# try.net
KiCad netlist of a schematic drawn in EAGLE
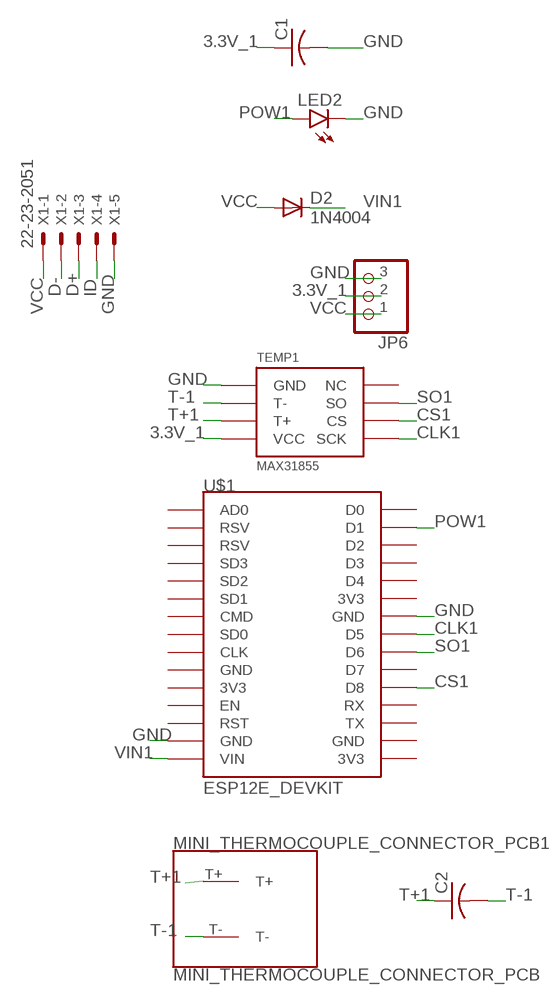
[diagram p0: schematic, sheet 1]

(export (version "E")
  (design (tool "Eeschema 10.0.6"))
  (components
    (comp (ref "C1")
      (value "C-US025-040X050")
      (footprint "eagle-import:C025-040X050")
      (libsource (lib "eagle-import") (part "C-US025-040X050"))
    )
    (comp (ref "C2")
      (value "C-US025-040X050")
      (footprint "eagle-import:C025-040X050")
      (libsource (lib "eagle-import") (part "C-US025-040X050"))
    )
    (comp (ref "D2")
      (value "1N4004")
      (footprint "eagle-import:DO41-10")
      (libsource (lib "eagle-import") (part "1N4004"))
    )
    (comp (ref "JP6")
      (value "PINHD-1X3CB")
      (footprint "eagle-import:1X03-CLEANBIG")
      (libsource (lib "eagle-import") (part "PINHD-1X3CB"))
    )
    (comp (ref "LED2")
      (value "LED5MM")
      (footprint "eagle-import:LED5MM")
      (libsource (lib "eagle-import") (part "LED5MM"))
    )
    (comp (ref "MINI_THERMOCOUPLE_CONNECTOR_PCB1")
      (value "MINI_THERMOCOUPLE_CONNECTOR_PCB")
      (footprint "eagle-import:MINI_THERMOCOUPLE_CONNECTOR_PCB")
      (libsource (lib "eagle-import") (part "MINI_THERMOCOUPLE_CONNECTOR_PCB"))
    )
    (comp (ref "TEMP1")
      (value "MAX31855")
      (footprint "eagle-import:SOIC-8")
      (libsource (lib "eagle-import") (part "MAX6675MAX31855"))
    )
    (comp (ref "U$1")
      (value "ESP12E_DEVKIT")
      (footprint "eagle-import:ESP12E_DEVKIT")
      (libsource (lib "eagle-import") (part "ESP12E_DEVKIT"))
    )
    (comp (ref "X1")
      (value "22-23-2051")
      (footprint "eagle-import:22-23-2051")
      (fields (field (name "MF") "MOLEX"))
      (libsource (lib "eagle-import") (part "22-23-2051"))
    )
  )
  (nets
    (net (code "1") (name "/3.3V_1") (class "Default")
      (node (ref "C1") (pin "1") (pinfunction "1_1") (pintype "passive"))
      (node (ref "JP6") (pin "2") (pinfunction "2_2") (pintype "passive"))
      (node (ref "TEMP1") (pin "VCC") (pinfunction "VCC_VCC") (pintype "bidirectional"))
    )
    (net (code "2") (name "/CLK1") (class "Default")
      (node (ref "TEMP1") (pin "SCK") (pinfunction "SCK_SCK") (pintype "bidirectional"))
      (node (ref "U$1") (pin "D5") (pinfunction "D5_D5") (pintype "bidirectional"))
    )
    (net (code "3") (name "/CS1") (class "Default")
      (node (ref "TEMP1") (pin "CS") (pinfunction "CS_CS") (pintype "bidirectional"))
      (node (ref "U$1") (pin "D8") (pinfunction "D8_D8") (pintype "bidirectional"))
    )
    (net (code "4") (name "/D+") (class "Default")
      (node (ref "X1") (pin "3") (pinfunction "S_3") (pintype "passive"))
    )
    (net (code "5") (name "/D-") (class "Default")
      (node (ref "X1") (pin "2") (pinfunction "S_2") (pintype "passive"))
    )
    (net (code "6") (name "/GND") (class "Default")
      (node (ref "C1") (pin "2") (pinfunction "2_2") (pintype "passive"))
      (node (ref "JP6") (pin "3") (pinfunction "3_3") (pintype "passive"))
      (node (ref "LED2") (pin "K") (pinfunction "C_K") (pintype "passive"))
      (node (ref "TEMP1") (pin "GND") (pinfunction "GND_GND") (pintype "bidirectional"))
      (node (ref "U$1") (pin "GND@1") (pinfunction "GND_GND@1") (pintype "bidirectional"))
      (node (ref "U$1") (pin "GND@2") (pinfunction "GND_GND@2") (pintype "bidirectional"))
      (node (ref "X1") (pin "5") (pinfunction "S_5") (pintype "passive"))
    )
    (net (code "7") (name "/ID") (class "Default")
      (node (ref "X1") (pin "4") (pinfunction "S_4") (pintype "passive"))
    )
    (net (code "8") (name "/POW1") (class "Default")
      (node (ref "LED2") (pin "A") (pinfunction "A_A") (pintype "passive"))
      (node (ref "U$1") (pin "D1") (pinfunction "D1_D1") (pintype "bidirectional"))
    )
    (net (code "9") (name "/SO1") (class "Default")
      (node (ref "TEMP1") (pin "SO") (pinfunction "SO_SO") (pintype "bidirectional"))
      (node (ref "U$1") (pin "D6") (pinfunction "D6_D6") (pintype "bidirectional"))
    )
    (net (code "10") (name "/T+1") (class "Default")
      (node (ref "C2") (pin "1") (pinfunction "1_1") (pintype "passive"))
      (node (ref "MINI_THERMOCOUPLE_CONNECTOR_PCB1") (pin "T+") (pinfunction "T+_T+") (pintype "bidirectional"))
      (node (ref "TEMP1") (pin "T+") (pinfunction "T+_T+") (pintype "bidirectional"))
    )
    (net (code "11") (name "/T-1") (class "Default")
      (node (ref "C2") (pin "2") (pinfunction "2_2") (pintype "passive"))
      (node (ref "MINI_THERMOCOUPLE_CONNECTOR_PCB1") (pin "T-") (pinfunction "T-_T-") (pintype "bidirectional"))
      (node (ref "TEMP1") (pin "T-") (pinfunction "T-_T-") (pintype "bidirectional"))
    )
    (net (code "12") (name "/VCC") (class "Default")
      (node (ref "D2") (pin "A") (pinfunction "A_A") (pintype "passive"))
      (node (ref "JP6") (pin "1") (pinfunction "1_1") (pintype "passive"))
      (node (ref "X1") (pin "1") (pinfunction "S_1") (pintype "passive"))
    )
    (net (code "13") (name "/VIN1") (class "Default")
      (node (ref "D2") (pin "C") (pinfunction "C_C") (pintype "passive"))
      (node (ref "U$1") (pin "VIN") (pinfunction "VIN_VIN") (pintype "bidirectional"))
    )
    (net (code "14") (name "unconnected-(TEMP1-PadNC)") (class "Default")
      (node (ref "TEMP1") (pin "NC") (pinfunction "NC_NC") (pintype "no_connect"))
    )
    (net (code "15") (name "unconnected-(U$1-3V3-Pad3V3@0)") (class "Default")
      (node (ref "U$1") (pin "3V3@0") (pinfunction "3V3_3V3@0") (pintype "bidirectional"))
    )
    (net (code "16") (name "unconnected-(U$1-3V3-Pad3V3@1)") (class "Default")
      (node (ref "U$1") (pin "3V3@1") (pinfunction "3V3_3V3@1") (pintype "bidirectional"))
    )
    (net (code "17") (name "unconnected-(U$1-3V3-Pad3V3@2)") (class "Default")
      (node (ref "U$1") (pin "3V3@2") (pinfunction "3V3_3V3@2") (pintype "bidirectional"))
    )
    (net (code "18") (name "unconnected-(U$1-GND-PadGND@0)") (class "Default")
      (node (ref "U$1") (pin "GND@0") (pinfunction "GND_GND@0") (pintype "bidirectional"))
    )
    (net (code "19") (name "unconnected-(U$1-GND-PadGND@3)") (class "Default")
      (node (ref "U$1") (pin "GND@3") (pinfunction "GND_GND@3") (pintype "bidirectional"))
    )
    (net (code "20") (name "unconnected-(U$1-PadAD0)") (class "Default")
      (node (ref "U$1") (pin "AD0") (pinfunction "AD0_AD0") (pintype "bidirectional"))
    )
    (net (code "21") (name "unconnected-(U$1-PadCLK)") (class "Default")
      (node (ref "U$1") (pin "CLK") (pinfunction "CLK_CLK") (pintype "bidirectional"))
    )
    (net (code "22") (name "unconnected-(U$1-PadCMD)") (class "Default")
      (node (ref "U$1") (pin "CMD") (pinfunction "CMD_CMD") (pintype "bidirectional"))
    )
    (net (code "23") (name "unconnected-(U$1-PadD0)") (class "Default")
      (node (ref "U$1") (pin "D0") (pinfunction "D0_D0") (pintype "bidirectional"))
    )
    (net (code "24") (name "unconnected-(U$1-PadD2)") (class "Default")
      (node (ref "U$1") (pin "D2") (pinfunction "D2_D2") (pintype "bidirectional"))
    )
    (net (code "25") (name "unconnected-(U$1-PadD3)") (class "Default")
      (node (ref "U$1") (pin "D3") (pinfunction "D3_D3") (pintype "bidirectional"))
    )
    (net (code "26") (name "unconnected-(U$1-PadD4)") (class "Default")
      (node (ref "U$1") (pin "D4") (pinfunction "D4_D4") (pintype "bidirectional"))
    )
    (net (code "27") (name "unconnected-(U$1-PadD7)") (class "Default")
      (node (ref "U$1") (pin "D7") (pinfunction "D7_D7") (pintype "bidirectional"))
    )
    (net (code "28") (name "unconnected-(U$1-PadEN)") (class "Default")
      (node (ref "U$1") (pin "EN") (pinfunction "EN_EN") (pintype "bidirectional"))
    )
    (net (code "29") (name "unconnected-(U$1-PadRST)") (class "Default")
      (node (ref "U$1") (pin "RST") (pinfunction "RST_RST") (pintype "bidirectional"))
    )
    (net (code "30") (name "unconnected-(U$1-PadRX)") (class "Default")
      (node (ref "U$1") (pin "RX") (pinfunction "RX_RX") (pintype "bidirectional"))
    )
    (net (code "31") (name "unconnected-(U$1-PadSD0)") (class "Default")
      (node (ref "U$1") (pin "SD0") (pinfunction "SD0_SD0") (pintype "bidirectional"))
    )
    (net (code "32") (name "unconnected-(U$1-PadSD1)") (class "Default")
      (node (ref "U$1") (pin "SD1") (pinfunction "SD1_SD1") (pintype "bidirectional"))
    )
    (net (code "33") (name "unconnected-(U$1-PadSD2)") (class "Default")
      (node (ref "U$1") (pin "SD2") (pinfunction "SD2_SD2") (pintype "bidirectional"))
    )
    (net (code "34") (name "unconnected-(U$1-PadSD3)") (class "Default")
      (node (ref "U$1") (pin "SD3") (pinfunction "SD3_SD3") (pintype "bidirectional"))
    )
    (net (code "35") (name "unconnected-(U$1-PadTX)") (class "Default")
      (node (ref "U$1") (pin "TX") (pinfunction "TX_TX") (pintype "bidirectional"))
    )
    (net (code "36") (name "unconnected-(U$1-RSV-PadRSV@0)") (class "Default")
      (node (ref "U$1") (pin "RSV@0") (pinfunction "RSV_RSV@0") (pintype "bidirectional"))
    )
    (net (code "37") (name "unconnected-(U$1-RSV-PadRSV@1)") (class "Default")
      (node (ref "U$1") (pin "RSV@1") (pinfunction "RSV_RSV@1") (pintype "bidirectional"))
    )
  )
)
